# rcstick-f-tiny.net
KiCad netlist of a schematic drawn in EAGLE
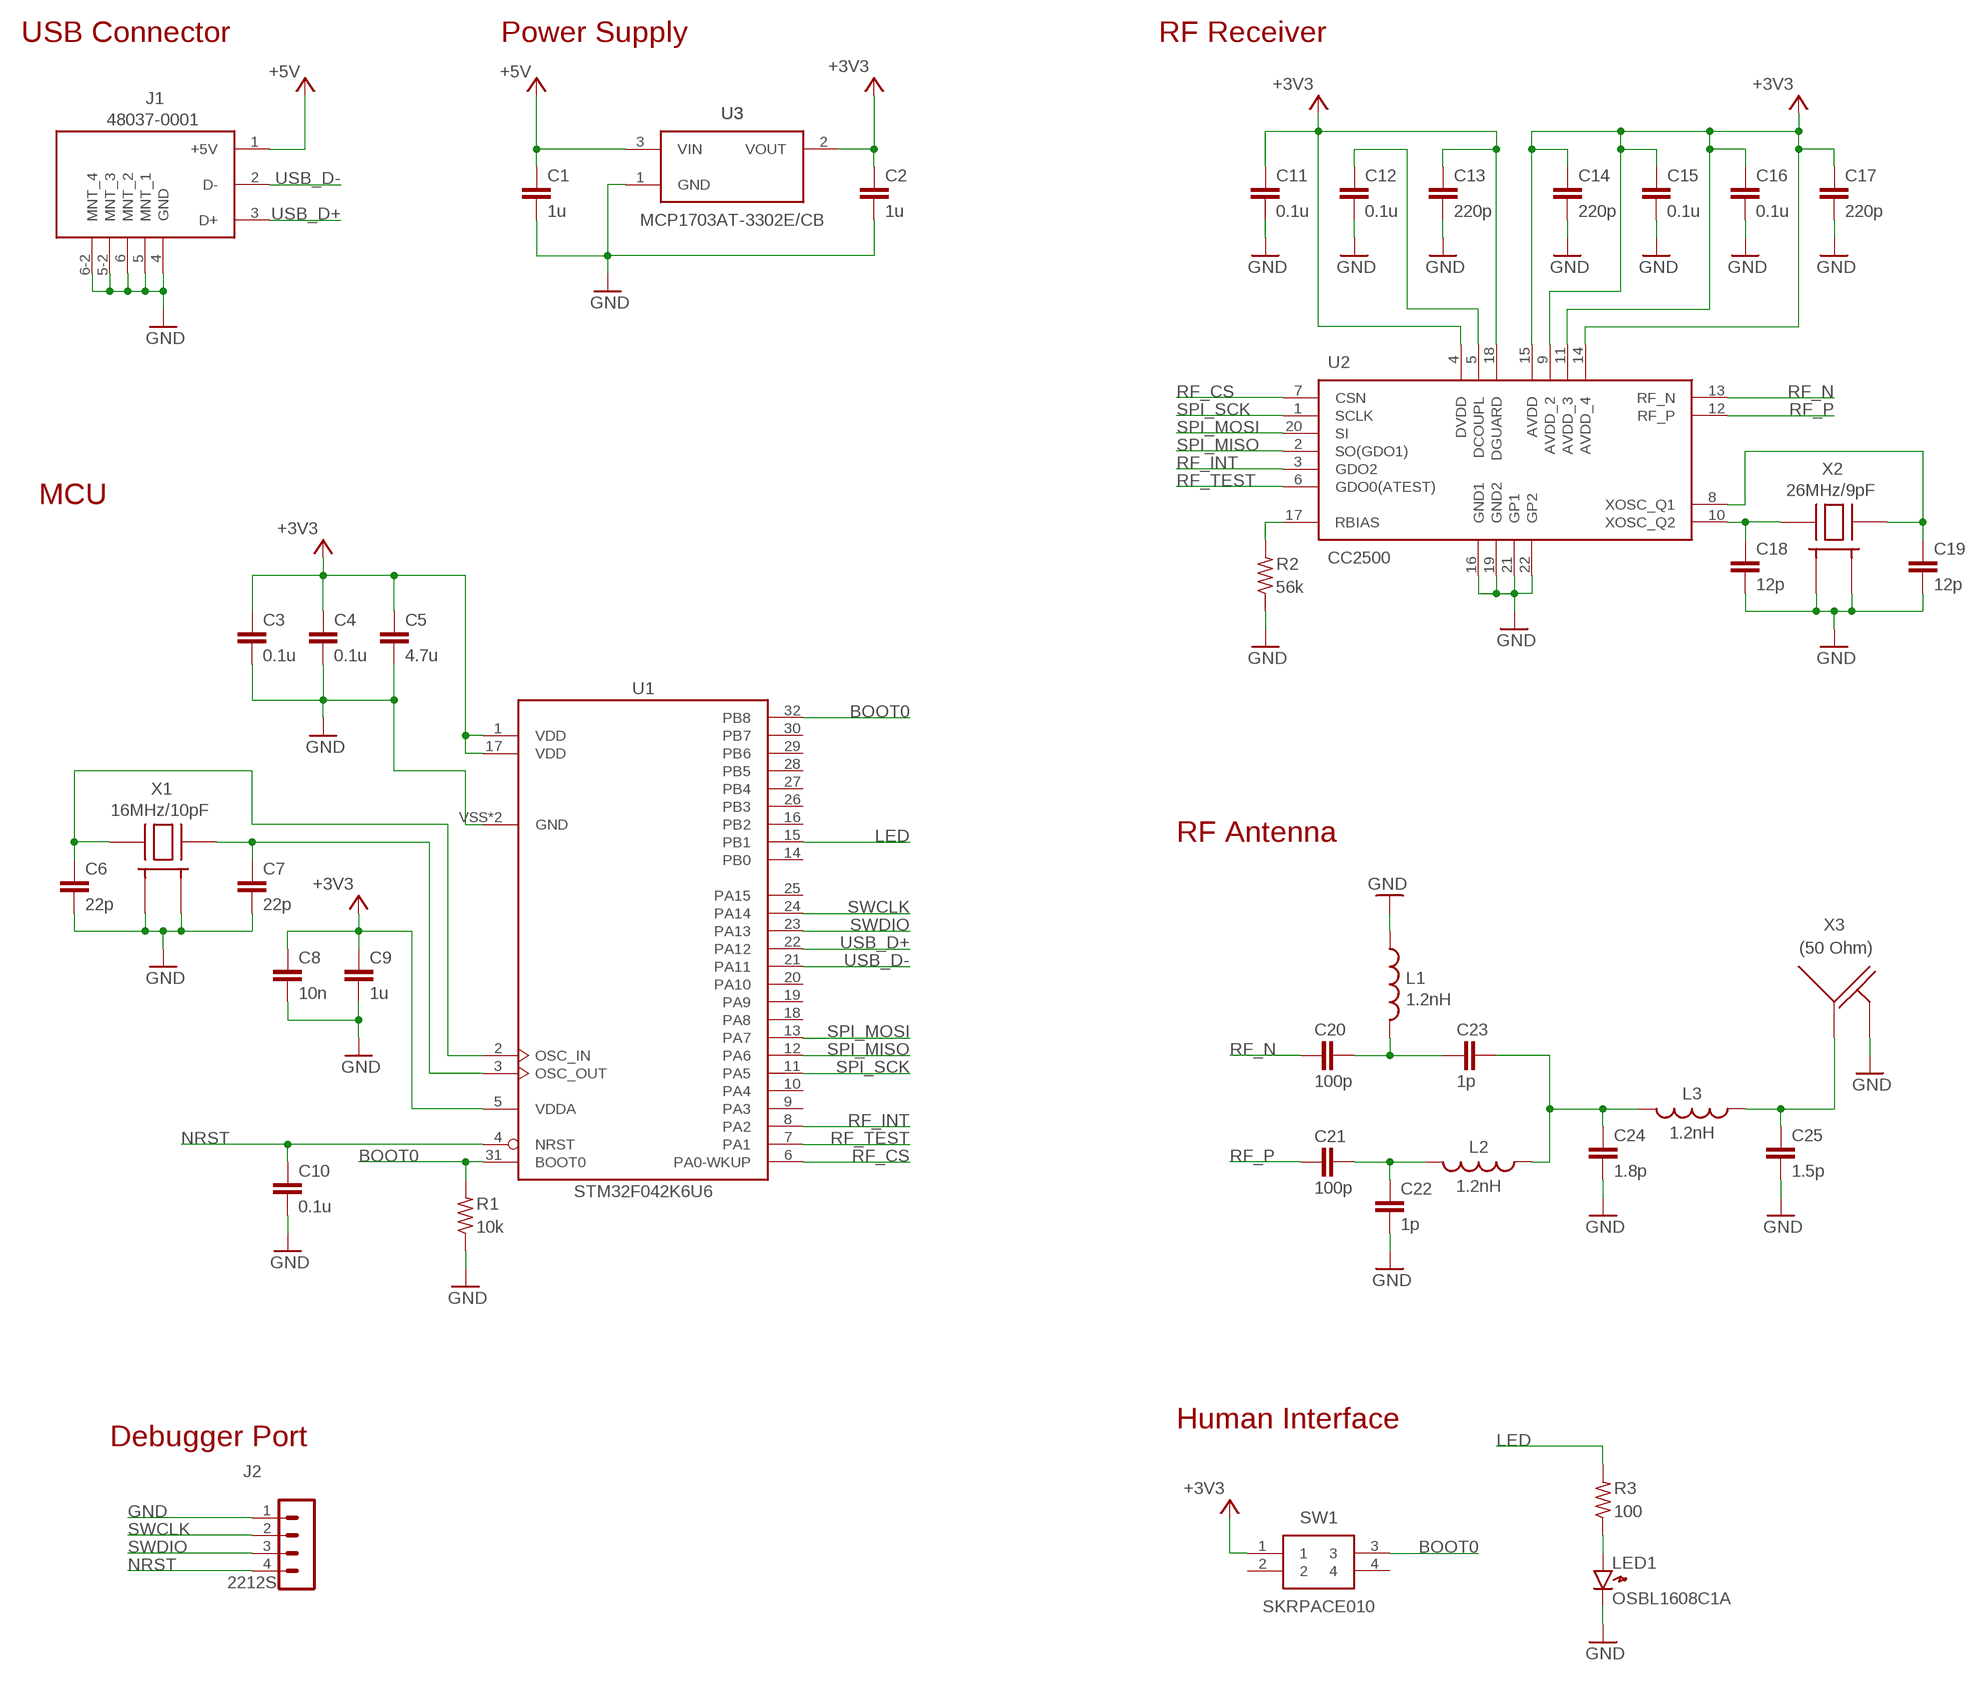
[diagram p0: schematic, sheet 1]

(export (version "E")
  (design (tool "Eeschema 10.0.6"))
  (components
    (comp (ref "C1")
      (value "1u")
      (footprint "eagle-import:RCL_C0402_HS")
      (libsource (lib "eagle-import") (part "RCL_C-EUC0402-HS"))
    )
    (comp (ref "C2")
      (value "1u")
      (footprint "eagle-import:RCL_C0402_HS")
      (libsource (lib "eagle-import") (part "RCL_C-EUC0402-HS"))
    )
    (comp (ref "C3")
      (value "0.1u")
      (footprint "eagle-import:RCL_C0402_HS")
      (libsource (lib "eagle-import") (part "RCL_C-EUC0402-HS"))
    )
    (comp (ref "C4")
      (value "0.1u")
      (footprint "eagle-import:RCL_C0402_HS")
      (libsource (lib "eagle-import") (part "RCL_C-EUC0402-HS"))
    )
    (comp (ref "C5")
      (value "4.7u")
      (footprint "eagle-import:RCL_C0402_HS")
      (libsource (lib "eagle-import") (part "RCL_C-EUC0402-HS"))
    )
    (comp (ref "C6")
      (value "22p")
      (footprint "eagle-import:RCL_C0402_HS")
      (libsource (lib "eagle-import") (part "RCL_C-EUC0402-HS"))
    )
    (comp (ref "C7")
      (value "22p")
      (footprint "eagle-import:RCL_C0402_HS")
      (libsource (lib "eagle-import") (part "RCL_C-EUC0402-HS"))
    )
    (comp (ref "C8")
      (value "10n")
      (footprint "eagle-import:RCL_C0402_HS")
      (libsource (lib "eagle-import") (part "RCL_C-EUC0402-HS"))
    )
    (comp (ref "C9")
      (value "1u")
      (footprint "eagle-import:RCL_C0402_HS")
      (libsource (lib "eagle-import") (part "RCL_C-EUC0402-HS"))
    )
    (comp (ref "C10")
      (value "0.1u")
      (footprint "eagle-import:RCL_C0402_HS")
      (libsource (lib "eagle-import") (part "RCL_C-EUC0402-HS"))
    )
    (comp (ref "C11")
      (value "0.1u")
      (footprint "eagle-import:RCL_C0402_HS")
      (libsource (lib "eagle-import") (part "RCL_C-EUC0402-HS"))
    )
    (comp (ref "C12")
      (value "0.1u")
      (footprint "eagle-import:RCL_C0402_HS")
      (libsource (lib "eagle-import") (part "RCL_C-EUC0402-HS"))
    )
    (comp (ref "C13")
      (value "220p")
      (footprint "eagle-import:RCL_C0402_HS")
      (libsource (lib "eagle-import") (part "RCL_C-EUC0402-HS"))
    )
    (comp (ref "C14")
      (value "220p")
      (footprint "eagle-import:RCL_C0402_HS")
      (libsource (lib "eagle-import") (part "RCL_C-EUC0402-HS"))
    )
    (comp (ref "C15")
      (value "0.1u")
      (footprint "eagle-import:RCL_C0402_HS")
      (libsource (lib "eagle-import") (part "RCL_C-EUC0402-HS"))
    )
    (comp (ref "C16")
      (value "0.1u")
      (footprint "eagle-import:RCL_C0402_HS")
      (libsource (lib "eagle-import") (part "RCL_C-EUC0402-HS"))
    )
    (comp (ref "C17")
      (value "220p")
      (footprint "eagle-import:RCL_C0402_HS")
      (libsource (lib "eagle-import") (part "RCL_C-EUC0402-HS"))
    )
    (comp (ref "C18")
      (value "12p")
      (footprint "eagle-import:RCL_C0402_HS")
      (libsource (lib "eagle-import") (part "RCL_C-EUC0402-HS"))
    )
    (comp (ref "C19")
      (value "12p")
      (footprint "eagle-import:RCL_C0402_HS")
      (libsource (lib "eagle-import") (part "RCL_C-EUC0402-HS"))
    )
    (comp (ref "C20")
      (value "100p")
      (footprint "eagle-import:RCL_C0402_HS")
      (libsource (lib "eagle-import") (part "RCL_C-EUC0402-HS"))
    )
    (comp (ref "C21")
      (value "100p")
      (footprint "eagle-import:RCL_C0402_HS")
      (libsource (lib "eagle-import") (part "RCL_C-EUC0402-HS"))
    )
    (comp (ref "C22")
      (value "1p")
      (footprint "eagle-import:RCL_C0402_HS")
      (libsource (lib "eagle-import") (part "RCL_C-EUC0402-HS"))
    )
    (comp (ref "C23")
      (value "1p")
      (footprint "eagle-import:RCL_C0402_HS")
      (libsource (lib "eagle-import") (part "RCL_C-EUC0402-HS"))
    )
    (comp (ref "C24")
      (value "1.8p")
      (footprint "eagle-import:RCL_C0402_HS")
      (libsource (lib "eagle-import") (part "RCL_C-EUC0402-HS"))
    )
    (comp (ref "C25")
      (value "1.5p")
      (footprint "eagle-import:RCL_C0402_HS")
      (libsource (lib "eagle-import") (part "RCL_C-EUC0402-HS"))
    )
    (comp (ref "J1")
      (value "MOLEX_48037-0001")
      (footprint "eagle-import:MOLEX_48037-0001_1")
      (libsource (lib "eagle-import") (part "MOLEX_48037-0001"))
    )
    (comp (ref "J2")
      (value "2212S")
      (footprint "eagle-import:53047-0410")
      (libsource (lib "eagle-import") (part "53047-0410"))
    )
    (comp (ref "L1")
      (value "1.2nH")
      (footprint "eagle-import:RCL_L0402_HS")
      (libsource (lib "eagle-import") (part "RCL_L-USL0402-HS"))
    )
    (comp (ref "L2")
      (value "1.2nH")
      (footprint "eagle-import:RCL_L0402_HS")
      (libsource (lib "eagle-import") (part "RCL_L-USL0402-HS"))
    )
    (comp (ref "L3")
      (value "1.2nH")
      (footprint "eagle-import:RCL_L0402_HS")
      (libsource (lib "eagle-import") (part "RCL_L-USL0402-HS"))
    )
    (comp (ref "LED1")
      (value "OSBL1608C1A")
      (footprint "eagle-import:LED1608")
      (libsource (lib "eagle-import") (part "LED1608"))
    )
    (comp (ref "R1")
      (value "10k")
      (footprint "eagle-import:RCL_R0402_HS")
      (libsource (lib "eagle-import") (part "RCL_R-US_R0402-HS"))
    )
    (comp (ref "R2")
      (value "56k")
      (footprint "eagle-import:RCL_R0402_HS")
      (libsource (lib "eagle-import") (part "RCL_R-US_R0402-HS"))
    )
    (comp (ref "R3")
      (value "100")
      (footprint "eagle-import:RCL_R0402_HS")
      (libsource (lib "eagle-import") (part "RCL_R-US_R0402-HS"))
    )
    (comp (ref "SW1")
      (value "SKRPACE010")
      (footprint "eagle-import:SMT(4.2X3.2)")
      (libsource (lib "eagle-import") (part "SKRPACE010"))
    )
    (comp (ref "U1")
      (value "STM32F042K6U6")
      (footprint "eagle-import:UQFPN32-M")
      (libsource (lib "eagle-import") (part "STM32F042K6U-M"))
    )
    (comp (ref "U2")
      (value "CC2500")
      (footprint "eagle-import:CC2500-RTY1_CC2500-HS")
      (libsource (lib "eagle-import") (part "CC2500-HS"))
    )
    (comp (ref "U3")
      (value "MCP1703AT-3302E/CB")
      (footprint "eagle-import:SOT23")
      (libsource (lib "eagle-import") (part "LDO-REGULATOR"))
    )
    (comp (ref "X1")
      (value "16MHz/10pF")
      (footprint "eagle-import:CRYSTAL3225-HS")
      (libsource (lib "eagle-import") (part "CRYSTAL3225HS"))
    )
    (comp (ref "X2")
      (value "26MHz/9pF")
      (footprint "eagle-import:CRYSTAL3225-HS")
      (libsource (lib "eagle-import") (part "CRYSTAL3225HS"))
    )
    (comp (ref "X3")
      (value "(50 Ohm)")
      (footprint "eagle-import:2.4GHZ-INVERTED-F-SMALL-FLIP")
      (libsource (lib "eagle-import") (part "2.4GHZ-INVERED-FSMALL-FLIP"))
    )
  )
  (nets
    (net (code "1") (name "+3V3") (class "Default")
      (node (ref "C11") (pin "1") (pinfunction "1_1") (pintype "passive"))
      (node (ref "C13") (pin "1") (pinfunction "1_1") (pintype "passive"))
      (node (ref "C14") (pin "1") (pinfunction "1_1") (pintype "passive"))
      (node (ref "C15") (pin "1") (pinfunction "1_1") (pintype "passive"))
      (node (ref "C16") (pin "1") (pinfunction "1_1") (pintype "passive"))
      (node (ref "C17") (pin "1") (pinfunction "1_1") (pintype "passive"))
      (node (ref "C2") (pin "1") (pinfunction "1_1") (pintype "passive"))
      (node (ref "C3") (pin "1") (pinfunction "1_1") (pintype "passive"))
      (node (ref "C4") (pin "1") (pinfunction "1_1") (pintype "passive"))
      (node (ref "C5") (pin "1") (pinfunction "1_1") (pintype "passive"))
      (node (ref "C8") (pin "1") (pinfunction "1_1") (pintype "passive"))
      (node (ref "C9") (pin "1") (pinfunction "1_1") (pintype "passive"))
      (node (ref "SW1") (pin "1") (pinfunction "1_1") (pintype "bidirectional"))
      (node (ref "U1") (pin "1") (pinfunction "VDD_1") (pintype "power_in"))
      (node (ref "U1") (pin "17") (pinfunction "VDD_17") (pintype "power_in"))
      (node (ref "U1") (pin "5") (pinfunction "VDDA_5") (pintype "power_in"))
      (node (ref "U2") (pin "11") (pinfunction "AVDD_3_11") (pintype "bidirectional"))
      (node (ref "U2") (pin "14") (pinfunction "AVDD_4_14") (pintype "bidirectional"))
      (node (ref "U2") (pin "15") (pinfunction "AVDD_15") (pintype "bidirectional"))
      (node (ref "U2") (pin "18") (pinfunction "DGUARD_18") (pintype "bidirectional"))
      (node (ref "U2") (pin "4") (pinfunction "DVDD_4") (pintype "bidirectional"))
      (node (ref "U2") (pin "9") (pinfunction "AVDD_2_9") (pintype "bidirectional"))
      (node (ref "U3") (pin "2") (pinfunction "VOUT_2") (pintype "bidirectional"))
    )
    (net (code "2") (name "+5V") (class "Default")
      (node (ref "C1") (pin "1") (pinfunction "1_1") (pintype "passive"))
      (node (ref "J1") (pin "1") (pinfunction "+5V_1") (pintype "bidirectional"))
      (node (ref "U3") (pin "3") (pinfunction "VIN_3") (pintype "bidirectional"))
    )
    (net (code "3") (name "/BOOT0") (class "Default")
      (node (ref "R1") (pin "2") (pinfunction "2_2") (pintype "passive"))
      (node (ref "SW1") (pin "3") (pinfunction "3_3") (pintype "bidirectional"))
      (node (ref "U1") (pin "31") (pinfunction "BOOT0_31") (pintype "input"))
      (node (ref "U1") (pin "32") (pinfunction "PB8_32") (pintype "bidirectional"))
    )
    (net (code "4") (name "/LED") (class "Default")
      (node (ref "R3") (pin "2") (pinfunction "2_2") (pintype "passive"))
      (node (ref "U1") (pin "15") (pinfunction "PB1_15") (pintype "bidirectional"))
    )
    (net (code "5") (name "/NRST") (class "Default")
      (node (ref "C10") (pin "1") (pinfunction "1_1") (pintype "passive"))
      (node (ref "J2") (pin "4") (pinfunction "4_4") (pintype "passive"))
      (node (ref "U1") (pin "4") (pinfunction "NRST_4") (pintype "bidirectional"))
    )
    (net (code "6") (name "/RF_CS") (class "Default")
      (node (ref "U1") (pin "6") (pinfunction "PA0-WKUP_6") (pintype "bidirectional"))
      (node (ref "U2") (pin "7") (pinfunction "CSN_7") (pintype "bidirectional"))
    )
    (net (code "7") (name "/RF_INT") (class "Default")
      (node (ref "U1") (pin "8") (pinfunction "PA2_8") (pintype "bidirectional"))
      (node (ref "U2") (pin "3") (pinfunction "GDO2_3") (pintype "bidirectional"))
    )
    (net (code "8") (name "/RF_N") (class "Default")
      (node (ref "C20") (pin "1") (pinfunction "1_1") (pintype "passive"))
      (node (ref "U2") (pin "13") (pinfunction "RF_N_13") (pintype "bidirectional"))
    )
    (net (code "9") (name "/RF_P") (class "Default")
      (node (ref "C21") (pin "1") (pinfunction "1_1") (pintype "passive"))
      (node (ref "U2") (pin "12") (pinfunction "RF_P_12") (pintype "bidirectional"))
    )
    (net (code "10") (name "/RF_TEST") (class "Default")
      (node (ref "U1") (pin "7") (pinfunction "PA1_7") (pintype "bidirectional"))
      (node (ref "U2") (pin "6") (pinfunction "GDO0(ATEST)_6") (pintype "bidirectional"))
    )
    (net (code "11") (name "/SPI_MISO") (class "Default")
      (node (ref "U1") (pin "12") (pinfunction "PA6_12") (pintype "bidirectional"))
      (node (ref "U2") (pin "2") (pinfunction "SO(GDO1)_2") (pintype "bidirectional"))
    )
    (net (code "12") (name "/SPI_MOSI") (class "Default")
      (node (ref "U1") (pin "13") (pinfunction "PA7_13") (pintype "bidirectional"))
      (node (ref "U2") (pin "20") (pinfunction "SI_20") (pintype "bidirectional"))
    )
    (net (code "13") (name "/SPI_SCK") (class "Default")
      (node (ref "U1") (pin "11") (pinfunction "PA5_11") (pintype "bidirectional"))
      (node (ref "U2") (pin "1") (pinfunction "SCLK_1") (pintype "bidirectional"))
    )
    (net (code "14") (name "/SWCLK") (class "Default")
      (node (ref "J2") (pin "2") (pinfunction "2_2") (pintype "passive"))
      (node (ref "U1") (pin "24") (pinfunction "PA14_24") (pintype "bidirectional"))
    )
    (net (code "15") (name "/SWDIO") (class "Default")
      (node (ref "J2") (pin "3") (pinfunction "3_3") (pintype "passive"))
      (node (ref "U1") (pin "23") (pinfunction "PA13_23") (pintype "bidirectional"))
    )
    (net (code "16") (name "/USB_D+") (class "Default")
      (node (ref "J1") (pin "3") (pinfunction "D+_3") (pintype "bidirectional"))
      (node (ref "U1") (pin "22") (pinfunction "PA12_22") (pintype "bidirectional"))
    )
    (net (code "17") (name "/USB_D-") (class "Default")
      (node (ref "J1") (pin "2") (pinfunction "D-_2") (pintype "bidirectional"))
      (node (ref "U1") (pin "21") (pinfunction "PA11_21") (pintype "bidirectional"))
    )
    (net (code "18") (name "GND") (class "Default")
      (node (ref "C1") (pin "2") (pinfunction "2_2") (pintype "passive"))
      (node (ref "C10") (pin "2") (pinfunction "2_2") (pintype "passive"))
      (node (ref "C11") (pin "2") (pinfunction "2_2") (pintype "passive"))
      (node (ref "C12") (pin "2") (pinfunction "2_2") (pintype "passive"))
      (node (ref "C13") (pin "2") (pinfunction "2_2") (pintype "passive"))
      (node (ref "C14") (pin "2") (pinfunction "2_2") (pintype "passive"))
      (node (ref "C15") (pin "2") (pinfunction "2_2") (pintype "passive"))
      (node (ref "C16") (pin "2") (pinfunction "2_2") (pintype "passive"))
      (node (ref "C17") (pin "2") (pinfunction "2_2") (pintype "passive"))
      (node (ref "C18") (pin "2") (pinfunction "2_2") (pintype "passive"))
      (node (ref "C19") (pin "2") (pinfunction "2_2") (pintype "passive"))
      (node (ref "C2") (pin "2") (pinfunction "2_2") (pintype "passive"))
      (node (ref "C22") (pin "2") (pinfunction "2_2") (pintype "passive"))
      (node (ref "C24") (pin "2") (pinfunction "2_2") (pintype "passive"))
      (node (ref "C25") (pin "2") (pinfunction "2_2") (pintype "passive"))
      (node (ref "C3") (pin "2") (pinfunction "2_2") (pintype "passive"))
      (node (ref "C4") (pin "2") (pinfunction "2_2") (pintype "passive"))
      (node (ref "C5") (pin "2") (pinfunction "2_2") (pintype "passive"))
      (node (ref "C6") (pin "2") (pinfunction "2_2") (pintype "passive"))
      (node (ref "C7") (pin "2") (pinfunction "2_2") (pintype "passive"))
      (node (ref "C8") (pin "2") (pinfunction "2_2") (pintype "passive"))
      (node (ref "C9") (pin "2") (pinfunction "2_2") (pintype "passive"))
      (node (ref "J1") (pin "4") (pinfunction "GND_4") (pintype "bidirectional"))
      (node (ref "J1") (pin "5") (pinfunction "MNT_1_5") (pintype "bidirectional"))
      (node (ref "J1") (pin "5-2") (pinfunction "MNT_3_5-2") (pintype "bidirectional"))
      (node (ref "J1") (pin "6") (pinfunction "MNT_2_6") (pintype "bidirectional"))
      (node (ref "J1") (pin "6-2") (pinfunction "MNT_4_6-2") (pintype "bidirectional"))
      (node (ref "J2") (pin "1") (pinfunction "1_1") (pintype "passive"))
      (node (ref "L1") (pin "1") (pinfunction "1_1") (pintype "passive"))
      (node (ref "LED1") (pin "K") (pinfunction "K_K") (pintype "passive"))
      (node (ref "R1") (pin "1") (pinfunction "1_1") (pintype "passive"))
      (node (ref "R2") (pin "1") (pinfunction "1_1") (pintype "passive"))
      (node (ref "U1") (pin "VSS") (pinfunction "GND_VSS") (pintype "power_in"))
      (node (ref "U1") (pin "VSSH") (pinfunction "GND_VSSH") (pintype "power_in"))
      (node (ref "U2") (pin "16") (pinfunction "GND1_16") (pintype "bidirectional"))
      (node (ref "U2") (pin "19") (pinfunction "GND2_19") (pintype "bidirectional"))
      (node (ref "U2") (pin "21") (pinfunction "GP1_21") (pintype "bidirectional"))
      (node (ref "U2") (pin "22") (pinfunction "GP2_22") (pintype "bidirectional"))
      (node (ref "U3") (pin "1") (pinfunction "GND_1") (pintype "bidirectional"))
      (node (ref "X1") (pin "2") (pinfunction "GND_1_2") (pintype "bidirectional"))
      (node (ref "X1") (pin "4") (pinfunction "GND_2_4") (pintype "bidirectional"))
      (node (ref "X2") (pin "2") (pinfunction "GND_1_2") (pintype "bidirectional"))
      (node (ref "X2") (pin "4") (pinfunction "GND_2_4") (pintype "bidirectional"))
      (node (ref "X3") (pin "2") (pinfunction "GND_2") (pintype "bidirectional"))
    )
    (net (code "19") (name "Net-(C20-Pad2)") (class "Default")
      (node (ref "C20") (pin "2") (pinfunction "2_2") (pintype "passive"))
      (node (ref "C23") (pin "1") (pinfunction "1_1") (pintype "passive"))
      (node (ref "L1") (pin "2") (pinfunction "2_2") (pintype "passive"))
    )
    (net (code "20") (name "Net-(C21-Pad2)") (class "Default")
      (node (ref "C21") (pin "2") (pinfunction "2_2") (pintype "passive"))
      (node (ref "C22") (pin "1") (pinfunction "1_1") (pintype "passive"))
      (node (ref "L2") (pin "2") (pinfunction "2_2") (pintype "passive"))
    )
    (net (code "21") (name "Net-(C23-Pad2)") (class "Default")
      (node (ref "C23") (pin "2") (pinfunction "2_2") (pintype "passive"))
      (node (ref "C24") (pin "1") (pinfunction "1_1") (pintype "passive"))
      (node (ref "L2") (pin "1") (pinfunction "1_1") (pintype "passive"))
      (node (ref "L3") (pin "2") (pinfunction "2_2") (pintype "passive"))
    )
    (net (code "22") (name "Net-(LED1-PadA)") (class "Default")
      (node (ref "LED1") (pin "A") (pinfunction "A_A") (pintype "passive"))
      (node (ref "R3") (pin "1") (pinfunction "1_1") (pintype "passive"))
    )
    (net (code "23") (name "Net-(U1-OSC_IN)") (class "Default")
      (node (ref "C6") (pin "1") (pinfunction "1_1") (pintype "passive"))
      (node (ref "U1") (pin "2") (pinfunction "OSC_IN_2") (pintype "bidirectional"))
      (node (ref "X1") (pin "1") (pinfunction "HOT_1_1") (pintype "bidirectional"))
    )
    (net (code "24") (name "Net-(U1-OSC_OUT)") (class "Default")
      (node (ref "C7") (pin "1") (pinfunction "1_1") (pintype "passive"))
      (node (ref "U1") (pin "3") (pinfunction "OSC_OUT_3") (pintype "bidirectional"))
      (node (ref "X1") (pin "3") (pinfunction "HOT_2_3") (pintype "bidirectional"))
    )
    (net (code "25") (name "Net-(U2-DCOUPL)") (class "Default")
      (node (ref "C12") (pin "1") (pinfunction "1_1") (pintype "passive"))
      (node (ref "U2") (pin "5") (pinfunction "DCOUPL_5") (pintype "bidirectional"))
    )
    (net (code "26") (name "Net-(U2-RBIAS)") (class "Default")
      (node (ref "R2") (pin "2") (pinfunction "2_2") (pintype "passive"))
      (node (ref "U2") (pin "17") (pinfunction "RBIAS_17") (pintype "bidirectional"))
    )
    (net (code "27") (name "Net-(U2-XOSC_Q1)") (class "Default")
      (node (ref "C19") (pin "1") (pinfunction "1_1") (pintype "passive"))
      (node (ref "U2") (pin "8") (pinfunction "XOSC_Q1_8") (pintype "bidirectional"))
      (node (ref "X2") (pin "3") (pinfunction "HOT_2_3") (pintype "bidirectional"))
    )
    (net (code "28") (name "Net-(U2-XOSC_Q2)") (class "Default")
      (node (ref "C18") (pin "1") (pinfunction "1_1") (pintype "passive"))
      (node (ref "U2") (pin "10") (pinfunction "XOSC_Q2_10") (pintype "bidirectional"))
      (node (ref "X2") (pin "1") (pinfunction "HOT_1_1") (pintype "bidirectional"))
    )
    (net (code "29") (name "Net-(X3-ANT)") (class "Default")
      (node (ref "C25") (pin "1") (pinfunction "1_1") (pintype "passive"))
      (node (ref "L3") (pin "1") (pinfunction "1_1") (pintype "passive"))
      (node (ref "X3") (pin "1") (pinfunction "ANT_1") (pintype "bidirectional"))
    )
    (net (code "30") (name "unconnected-(SW1-Pad2)") (class "Default")
      (node (ref "SW1") (pin "2") (pinfunction "2_2") (pintype "bidirectional"))
    )
    (net (code "31") (name "unconnected-(SW1-Pad4)") (class "Default")
      (node (ref "SW1") (pin "4") (pinfunction "4_4") (pintype "bidirectional"))
    )
    (net (code "32") (name "unconnected-(U1-PA3-Pad9)") (class "Default")
      (node (ref "U1") (pin "9") (pinfunction "PA3_9") (pintype "bidirectional"))
    )
    (net (code "33") (name "unconnected-(U1-PA4-Pad10)") (class "Default")
      (node (ref "U1") (pin "10") (pinfunction "PA4_10") (pintype "bidirectional"))
    )
    (net (code "34") (name "unconnected-(U1-PA8-Pad18)") (class "Default")
      (node (ref "U1") (pin "18") (pinfunction "PA8_18") (pintype "bidirectional"))
    )
    (net (code "35") (name "unconnected-(U1-PA9-Pad19)") (class "Default")
      (node (ref "U1") (pin "19") (pinfunction "PA9_19") (pintype "bidirectional"))
    )
    (net (code "36") (name "unconnected-(U1-PA10-Pad20)") (class "Default")
      (node (ref "U1") (pin "20") (pinfunction "PA10_20") (pintype "bidirectional"))
    )
    (net (code "37") (name "unconnected-(U1-PA15-Pad25)") (class "Default")
      (node (ref "U1") (pin "25") (pinfunction "PA15_25") (pintype "bidirectional"))
    )
    (net (code "38") (name "unconnected-(U1-PB0-Pad14)") (class "Default")
      (node (ref "U1") (pin "14") (pinfunction "PB0_14") (pintype "bidirectional"))
    )
    (net (code "39") (name "unconnected-(U1-PB2-Pad16)") (class "Default")
      (node (ref "U1") (pin "16") (pinfunction "PB2_16") (pintype "bidirectional"))
    )
    (net (code "40") (name "unconnected-(U1-PB3-Pad26)") (class "Default")
      (node (ref "U1") (pin "26") (pinfunction "PB3_26") (pintype "bidirectional"))
    )
    (net (code "41") (name "unconnected-(U1-PB4-Pad27)") (class "Default")
      (node (ref "U1") (pin "27") (pinfunction "PB4_27") (pintype "bidirectional"))
    )
    (net (code "42") (name "unconnected-(U1-PB5-Pad28)") (class "Default")
      (node (ref "U1") (pin "28") (pinfunction "PB5_28") (pintype "bidirectional"))
    )
    (net (code "43") (name "unconnected-(U1-PB6-Pad29)") (class "Default")
      (node (ref "U1") (pin "29") (pinfunction "PB6_29") (pintype "bidirectional"))
    )
    (net (code "44") (name "unconnected-(U1-PB7-Pad30)") (class "Default")
      (node (ref "U1") (pin "30") (pinfunction "PB7_30") (pintype "bidirectional"))
    )
  )
)
